# Esquema_reloj_pov.net
KiCad netlist of a schematic drawn in EAGLE
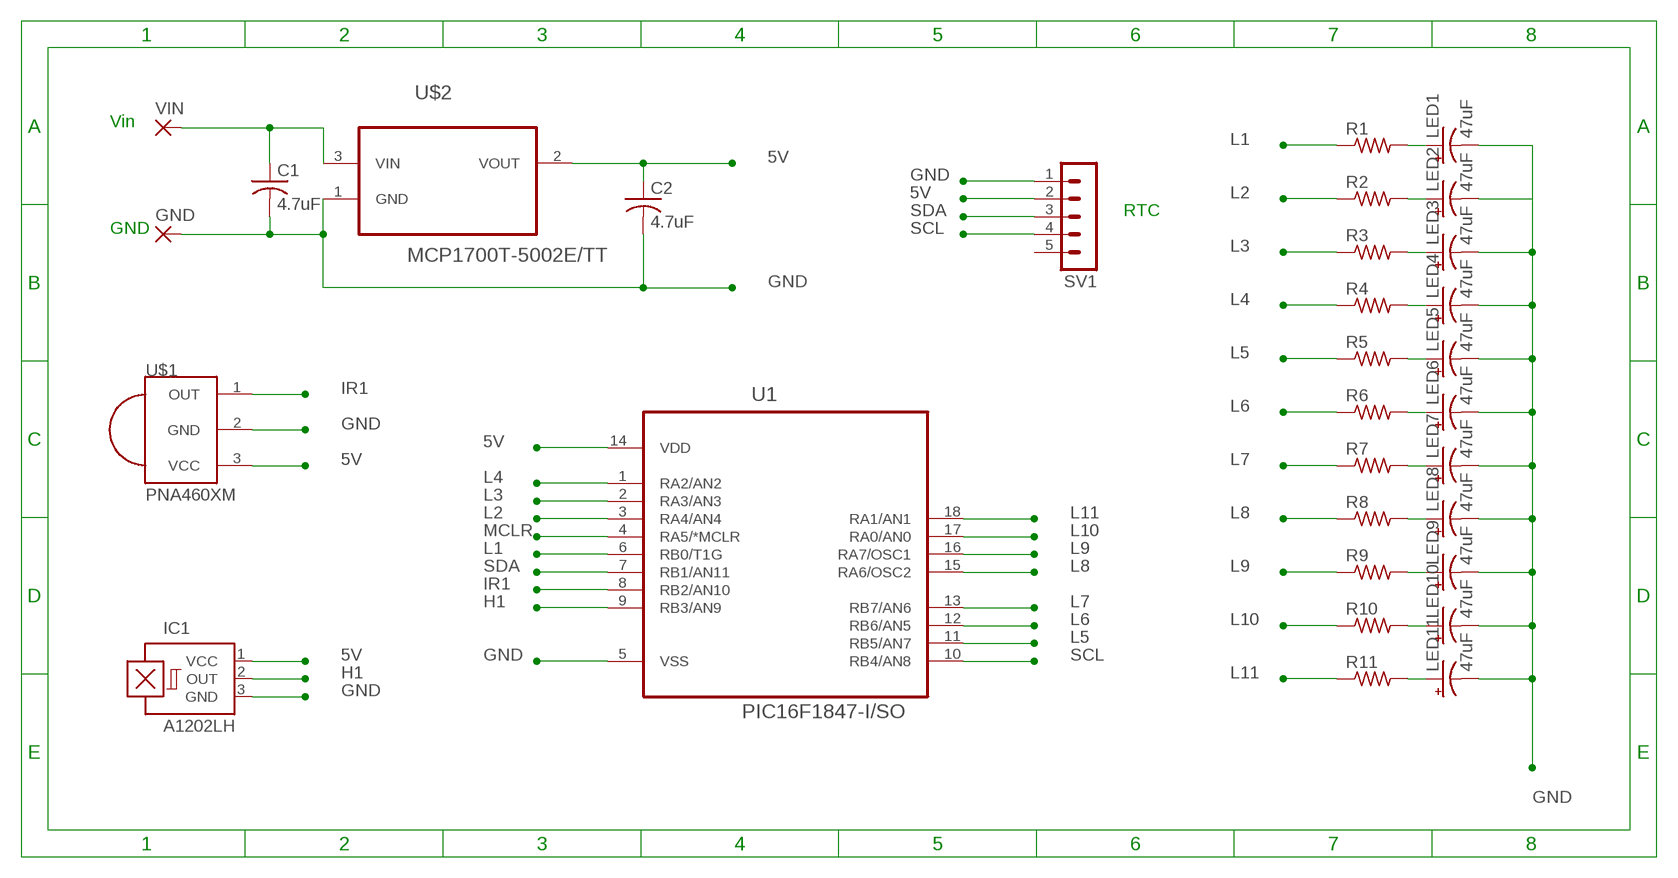
[diagram p0: schematic, sheet 1]

(export (version "E")
  (design (tool "Eeschema 10.0.6"))
  (components
    (comp (ref "C1")
      (value "4.7uF")
      (footprint "eagle-import:C0805K")
      (libsource (lib "eagle-import") (part "C-USC0805K"))
    )
    (comp (ref "C2")
      (value "4.7uF")
      (footprint "eagle-import:C0805K")
      (libsource (lib "eagle-import") (part "C-USC0805K"))
    )
    (comp (ref "GND")
      (value "2,54/0,8")
      (footprint "eagle-import:2,54_0,8")
      (libsource (lib "eagle-import") (part "2,54/0,8"))
    )
    (comp (ref "IC1")
      (value "A1202LH")
      (footprint "eagle-import:SOT23-W")
      (libsource (lib "eagle-import") (part "A12?LH02"))
    )
    (comp (ref "LED1")
      (value "47uF")
      (footprint "eagle-import:EIA3528")
      (libsource (lib "eagle-import") (part "47UF-10V-10%(TANT)"))
    )
    (comp (ref "LED2")
      (value "47uF")
      (footprint "eagle-import:EIA3528")
      (libsource (lib "eagle-import") (part "47UF-10V-10%(TANT)"))
    )
    (comp (ref "LED3")
      (value "47uF")
      (footprint "eagle-import:EIA3528")
      (libsource (lib "eagle-import") (part "47UF-10V-10%(TANT)"))
    )
    (comp (ref "LED4")
      (value "47uF")
      (footprint "eagle-import:EIA3528")
      (libsource (lib "eagle-import") (part "47UF-10V-10%(TANT)"))
    )
    (comp (ref "LED5")
      (value "47uF")
      (footprint "eagle-import:EIA3528")
      (libsource (lib "eagle-import") (part "47UF-10V-10%(TANT)"))
    )
    (comp (ref "LED6")
      (value "47uF")
      (footprint "eagle-import:EIA3528")
      (libsource (lib "eagle-import") (part "47UF-10V-10%(TANT)"))
    )
    (comp (ref "LED7")
      (value "47uF")
      (footprint "eagle-import:EIA3528")
      (libsource (lib "eagle-import") (part "47UF-10V-10%(TANT)"))
    )
    (comp (ref "LED8")
      (value "47uF")
      (footprint "eagle-import:EIA3528")
      (libsource (lib "eagle-import") (part "47UF-10V-10%(TANT)"))
    )
    (comp (ref "LED9")
      (value "47uF")
      (footprint "eagle-import:EIA3528")
      (libsource (lib "eagle-import") (part "47UF-10V-10%(TANT)"))
    )
    (comp (ref "LED10")
      (value "47uF")
      (footprint "eagle-import:EIA3528")
      (libsource (lib "eagle-import") (part "47UF-10V-10%(TANT)"))
    )
    (comp (ref "LED11")
      (value "47uF")
      (footprint "eagle-import:EIA3528")
      (libsource (lib "eagle-import") (part "47UF-10V-10%(TANT)"))
    )
    (comp (ref "R1")
      (value "R-US_R0805")
      (footprint "eagle-import:R0805")
      (libsource (lib "eagle-import") (part "R-US_R0805"))
    )
    (comp (ref "R2")
      (value "R-US_R0805")
      (footprint "eagle-import:R0805")
      (libsource (lib "eagle-import") (part "R-US_R0805"))
    )
    (comp (ref "R3")
      (value "R-US_R0805")
      (footprint "eagle-import:R0805")
      (libsource (lib "eagle-import") (part "R-US_R0805"))
    )
    (comp (ref "R4")
      (value "R-US_R0805")
      (footprint "eagle-import:R0805")
      (libsource (lib "eagle-import") (part "R-US_R0805"))
    )
    (comp (ref "R5")
      (value "R-US_R0805")
      (footprint "eagle-import:R0805")
      (libsource (lib "eagle-import") (part "R-US_R0805"))
    )
    (comp (ref "R6")
      (value "R-US_R0805")
      (footprint "eagle-import:R0805")
      (libsource (lib "eagle-import") (part "R-US_R0805"))
    )
    (comp (ref "R7")
      (value "R-US_R0805")
      (footprint "eagle-import:R0805")
      (libsource (lib "eagle-import") (part "R-US_R0805"))
    )
    (comp (ref "R8")
      (value "R-US_R0805")
      (footprint "eagle-import:R0805")
      (libsource (lib "eagle-import") (part "R-US_R0805"))
    )
    (comp (ref "R9")
      (value "R-US_R0805")
      (footprint "eagle-import:R0805")
      (libsource (lib "eagle-import") (part "R-US_R0805"))
    )
    (comp (ref "R10")
      (value "R-US_R0805")
      (footprint "eagle-import:R0805")
      (libsource (lib "eagle-import") (part "R-US_R0805"))
    )
    (comp (ref "R11")
      (value "R-US_R0805")
      (footprint "eagle-import:R0805")
      (libsource (lib "eagle-import") (part "R-US_R0805"))
    )
    (comp (ref "SV1")
      (value "MA05-1")
      (footprint "eagle-import:MA05-1")
      (libsource (lib "eagle-import") (part "MA05-1"))
    )
    (comp (ref "U$1")
      (value "PNA460XM")
      (footprint "eagle-import:PNA460XM")
      (libsource (lib "eagle-import") (part "PNA460XM"))
    )
    (comp (ref "U$2")
      (value "MCP1700T-5002E/TT")
      (footprint "eagle-import:SOT95P237X112-3N")
      (libsource (lib "eagle-import") (part "MCP1700T-5002E/TT"))
    )
    (comp (ref "U1")
      (value "PIC16F1847-I/SO")
      (footprint "eagle-import:SOIC127P1030X265-18N")
      (libsource (lib "eagle-import") (part "PIC16F1847-I/SO"))
    )
    (comp (ref "VIN")
      (value "2,54/0,8")
      (footprint "eagle-import:2,54_0,8")
      (libsource (lib "eagle-import") (part "2,54/0,8"))
    )
  )
  (nets
    (net (code "1") (name "/5V") (class "Default")
      (node (ref "C2") (pin "1") (pinfunction "1_1") (pintype "passive"))
      (node (ref "IC1") (pin "1") (pinfunction "VCC_1") (pintype "power_in"))
      (node (ref "SV1") (pin "2") (pinfunction "2_2") (pintype "passive"))
      (node (ref "U$1") (pin "3") (pinfunction "VCC_3") (pintype "power_in"))
      (node (ref "U$2") (pin "2") (pinfunction "VOUT_2") (pintype "output"))
      (node (ref "U1") (pin "14") (pinfunction "VDD_14") (pintype "power_in"))
    )
    (net (code "2") (name "/GND") (class "Default")
      (node (ref "C1") (pin "2") (pinfunction "2_2") (pintype "passive"))
      (node (ref "C2") (pin "2") (pinfunction "2_2") (pintype "passive"))
      (node (ref "GND") (pin "1") (pinfunction "P_1") (pintype "passive"))
      (node (ref "IC1") (pin "3") (pinfunction "GND_3") (pintype "power_in"))
      (node (ref "LED1") (pin "C") (pinfunction "-_C") (pintype "passive"))
      (node (ref "LED10") (pin "C") (pinfunction "-_C") (pintype "passive"))
      (node (ref "LED11") (pin "C") (pinfunction "-_C") (pintype "passive"))
      (node (ref "LED2") (pin "C") (pinfunction "-_C") (pintype "passive"))
      (node (ref "LED3") (pin "C") (pinfunction "-_C") (pintype "passive"))
      (node (ref "LED4") (pin "C") (pinfunction "-_C") (pintype "passive"))
      (node (ref "LED5") (pin "C") (pinfunction "-_C") (pintype "passive"))
      (node (ref "LED6") (pin "C") (pinfunction "-_C") (pintype "passive"))
      (node (ref "LED7") (pin "C") (pinfunction "-_C") (pintype "passive"))
      (node (ref "LED8") (pin "C") (pinfunction "-_C") (pintype "passive"))
      (node (ref "LED9") (pin "C") (pinfunction "-_C") (pintype "passive"))
      (node (ref "SV1") (pin "1") (pinfunction "1_1") (pintype "passive"))
      (node (ref "U$1") (pin "2") (pinfunction "GND_2") (pintype "power_in"))
      (node (ref "U$2") (pin "1") (pinfunction "GND_1") (pintype "passive"))
      (node (ref "U1") (pin "5") (pinfunction "VSS_5") (pintype "power_in"))
    )
    (net (code "3") (name "/H1") (class "Default")
      (node (ref "IC1") (pin "2") (pinfunction "OUT_2") (pintype "output"))
      (node (ref "U1") (pin "9") (pinfunction "RB3/AN9_9") (pintype "bidirectional"))
    )
    (net (code "4") (name "/IR1") (class "Default")
      (node (ref "U$1") (pin "1") (pinfunction "OUT_1") (pintype "output"))
      (node (ref "U1") (pin "8") (pinfunction "RB2/AN10_8") (pintype "bidirectional"))
    )
    (net (code "5") (name "/L1") (class "Default")
      (node (ref "R1") (pin "1") (pinfunction "1_1") (pintype "passive"))
      (node (ref "U1") (pin "6") (pinfunction "RB0/T1G_6") (pintype "bidirectional"))
    )
    (net (code "6") (name "/L2") (class "Default")
      (node (ref "R2") (pin "1") (pinfunction "1_1") (pintype "passive"))
      (node (ref "U1") (pin "3") (pinfunction "RA4/AN4_3") (pintype "bidirectional"))
    )
    (net (code "7") (name "/L3") (class "Default")
      (node (ref "R3") (pin "1") (pinfunction "1_1") (pintype "passive"))
      (node (ref "U1") (pin "2") (pinfunction "RA3/AN3_2") (pintype "bidirectional"))
    )
    (net (code "8") (name "/L4") (class "Default")
      (node (ref "R4") (pin "1") (pinfunction "1_1") (pintype "passive"))
      (node (ref "U1") (pin "1") (pinfunction "RA2/AN2_1") (pintype "bidirectional"))
    )
    (net (code "9") (name "/L5") (class "Default")
      (node (ref "R5") (pin "1") (pinfunction "1_1") (pintype "passive"))
      (node (ref "U1") (pin "11") (pinfunction "RB5/AN7_11") (pintype "bidirectional"))
    )
    (net (code "10") (name "/L6") (class "Default")
      (node (ref "R6") (pin "1") (pinfunction "1_1") (pintype "passive"))
      (node (ref "U1") (pin "12") (pinfunction "RB6/AN5_12") (pintype "bidirectional"))
    )
    (net (code "11") (name "/L7") (class "Default")
      (node (ref "R7") (pin "1") (pinfunction "1_1") (pintype "passive"))
      (node (ref "U1") (pin "13") (pinfunction "RB7/AN6_13") (pintype "bidirectional"))
    )
    (net (code "12") (name "/L8") (class "Default")
      (node (ref "R8") (pin "1") (pinfunction "1_1") (pintype "passive"))
      (node (ref "U1") (pin "15") (pinfunction "RA6/OSC2_15") (pintype "bidirectional"))
    )
    (net (code "13") (name "/L9") (class "Default")
      (node (ref "R9") (pin "1") (pinfunction "1_1") (pintype "passive"))
      (node (ref "U1") (pin "16") (pinfunction "RA7/OSC1_16") (pintype "bidirectional"))
    )
    (net (code "14") (name "/L10") (class "Default")
      (node (ref "R10") (pin "1") (pinfunction "1_1") (pintype "passive"))
      (node (ref "U1") (pin "17") (pinfunction "RA0/AN0_17") (pintype "bidirectional"))
    )
    (net (code "15") (name "/L11") (class "Default")
      (node (ref "R11") (pin "1") (pinfunction "1_1") (pintype "passive"))
      (node (ref "U1") (pin "18") (pinfunction "RA1/AN1_18") (pintype "bidirectional"))
    )
    (net (code "16") (name "/MCLR") (class "Default")
      (node (ref "U1") (pin "4") (pinfunction "RA5/*MCLR_4") (pintype "bidirectional"))
    )
    (net (code "17") (name "/SCL") (class "Default")
      (node (ref "SV1") (pin "4") (pinfunction "4_4") (pintype "passive"))
      (node (ref "U1") (pin "10") (pinfunction "RB4/AN8_10") (pintype "bidirectional"))
    )
    (net (code "18") (name "/SDA") (class "Default")
      (node (ref "SV1") (pin "3") (pinfunction "3_3") (pintype "passive"))
      (node (ref "U1") (pin "7") (pinfunction "RB1/AN11_7") (pintype "bidirectional"))
    )
    (net (code "19") (name "Net-(LED1-+)") (class "Default")
      (node (ref "LED1") (pin "A") (pinfunction "+_A") (pintype "passive"))
      (node (ref "R1") (pin "2") (pinfunction "2_2") (pintype "passive"))
    )
    (net (code "20") (name "Net-(LED2-+)") (class "Default")
      (node (ref "LED2") (pin "A") (pinfunction "+_A") (pintype "passive"))
      (node (ref "R2") (pin "2") (pinfunction "2_2") (pintype "passive"))
    )
    (net (code "21") (name "Net-(LED3-+)") (class "Default")
      (node (ref "LED3") (pin "A") (pinfunction "+_A") (pintype "passive"))
      (node (ref "R3") (pin "2") (pinfunction "2_2") (pintype "passive"))
    )
    (net (code "22") (name "Net-(LED4-+)") (class "Default")
      (node (ref "LED4") (pin "A") (pinfunction "+_A") (pintype "passive"))
      (node (ref "R4") (pin "2") (pinfunction "2_2") (pintype "passive"))
    )
    (net (code "23") (name "Net-(LED5-+)") (class "Default")
      (node (ref "LED5") (pin "A") (pinfunction "+_A") (pintype "passive"))
      (node (ref "R5") (pin "2") (pinfunction "2_2") (pintype "passive"))
    )
    (net (code "24") (name "Net-(LED6-+)") (class "Default")
      (node (ref "LED6") (pin "A") (pinfunction "+_A") (pintype "passive"))
      (node (ref "R6") (pin "2") (pinfunction "2_2") (pintype "passive"))
    )
    (net (code "25") (name "Net-(LED7-+)") (class "Default")
      (node (ref "LED7") (pin "A") (pinfunction "+_A") (pintype "passive"))
      (node (ref "R7") (pin "2") (pinfunction "2_2") (pintype "passive"))
    )
    (net (code "26") (name "Net-(LED8-+)") (class "Default")
      (node (ref "LED8") (pin "A") (pinfunction "+_A") (pintype "passive"))
      (node (ref "R8") (pin "2") (pinfunction "2_2") (pintype "passive"))
    )
    (net (code "27") (name "Net-(LED9-+)") (class "Default")
      (node (ref "LED9") (pin "A") (pinfunction "+_A") (pintype "passive"))
      (node (ref "R9") (pin "2") (pinfunction "2_2") (pintype "passive"))
    )
    (net (code "28") (name "Net-(LED10-+)") (class "Default")
      (node (ref "LED10") (pin "A") (pinfunction "+_A") (pintype "passive"))
      (node (ref "R10") (pin "2") (pinfunction "2_2") (pintype "passive"))
    )
    (net (code "29") (name "Net-(LED11-+)") (class "Default")
      (node (ref "LED11") (pin "A") (pinfunction "+_A") (pintype "passive"))
      (node (ref "R11") (pin "2") (pinfunction "2_2") (pintype "passive"))
    )
    (net (code "30") (name "Net-(U$2-VIN)") (class "Default")
      (node (ref "C1") (pin "1") (pinfunction "1_1") (pintype "passive"))
      (node (ref "U$2") (pin "3") (pinfunction "VIN_3") (pintype "input"))
      (node (ref "VIN") (pin "1") (pinfunction "P_1") (pintype "passive"))
    )
    (net (code "31") (name "unconnected-(SV1-Pad5)") (class "Default")
      (node (ref "SV1") (pin "5") (pinfunction "5_5") (pintype "passive"))
    )
  )
)
